# pads.net
KiCad netlist of a schematic drawn in EAGLE
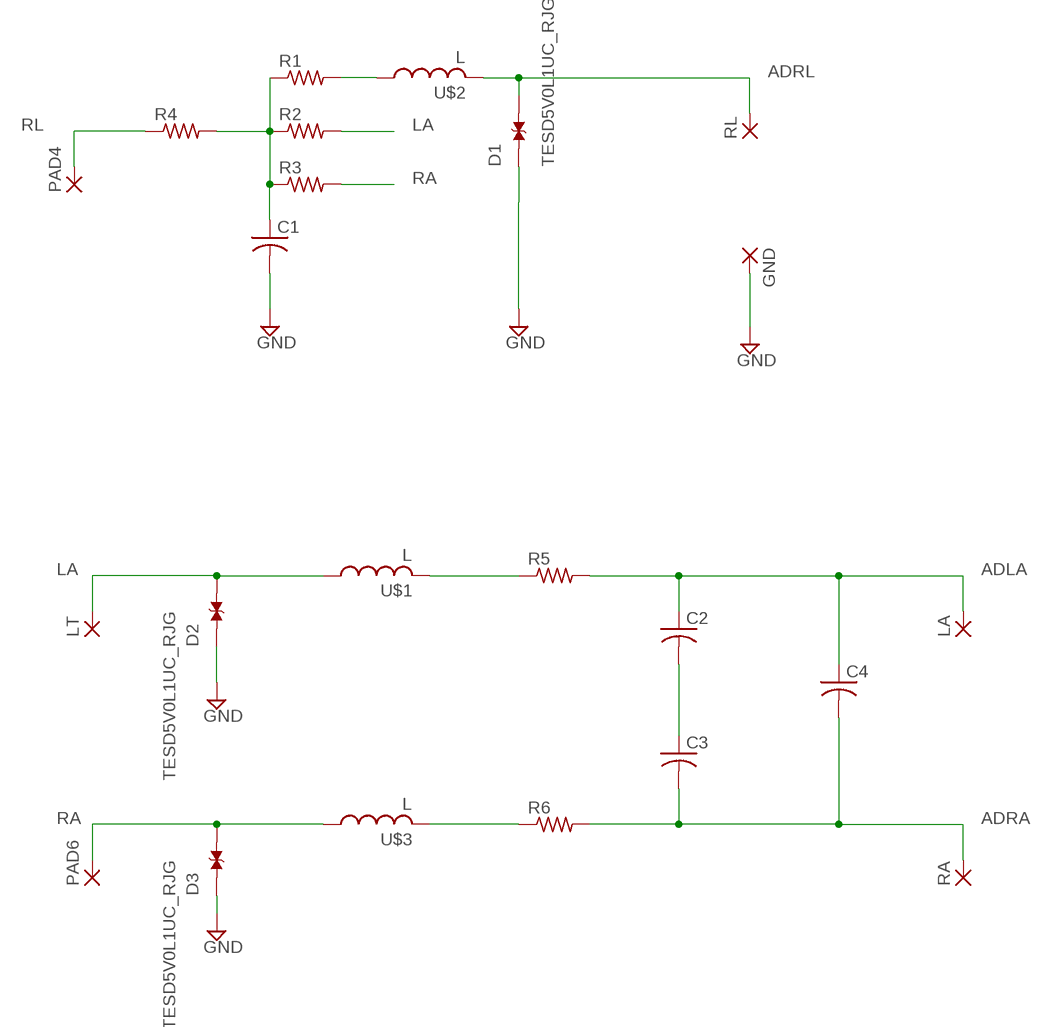
[diagram p0: schematic, sheet 1]

(export (version "E")
  (design (tool "Eeschema 10.0.6"))
  (components
    (comp (ref "C1")
      (value "C-US025-024X044")
      (footprint "eagle-import:C025-024X044")
      (libsource (lib "eagle-import") (part "C-US025-024X044"))
    )
    (comp (ref "C2")
      (value "C-US025-024X044")
      (footprint "eagle-import:C025-024X044")
      (libsource (lib "eagle-import") (part "C-US025-024X044"))
    )
    (comp (ref "C3")
      (value "C-US025-024X044")
      (footprint "eagle-import:C025-024X044")
      (libsource (lib "eagle-import") (part "C-US025-024X044"))
    )
    (comp (ref "C4")
      (value "C-US025-024X044")
      (footprint "eagle-import:C025-024X044")
      (libsource (lib "eagle-import") (part "C-US025-024X044"))
    )
    (comp (ref "D1")
      (value "TESD5V0L1UC_RJG")
      (footprint "eagle-import:DIO_TESD5V0L1UC_RJG")
      (fields (field (name "MF") "Taiwan Semiconductor Corporation") (field (name "MP") "TESD5V0L1UC RJG"))
      (libsource (lib "eagle-import") (part "TESD5V0L1UC_RJG"))
    )
    (comp (ref "D2")
      (value "TESD5V0L1UC_RJG")
      (footprint "eagle-import:DIO_TESD5V0L1UC_RJG")
      (fields (field (name "MF") "Taiwan Semiconductor Corporation") (field (name "MP") "TESD5V0L1UC RJG"))
      (libsource (lib "eagle-import") (part "TESD5V0L1UC_RJG"))
    )
    (comp (ref "D3")
      (value "TESD5V0L1UC_RJG")
      (footprint "eagle-import:DIO_TESD5V0L1UC_RJG")
      (fields (field (name "MF") "Taiwan Semiconductor Corporation") (field (name "MP") "TESD5V0L1UC RJG"))
      (libsource (lib "eagle-import") (part "TESD5V0L1UC_RJG"))
    )
    (comp (ref "GND")
      (value "2,15/1,0")
      (footprint "eagle-import:2,15_1,0")
      (libsource (lib "eagle-import") (part "2,15/1,0"))
    )
    (comp (ref "LA")
      (value "2,15/1,0")
      (footprint "eagle-import:2,15_1,0")
      (libsource (lib "eagle-import") (part "2,15/1,0"))
    )
    (comp (ref "LT")
      (value "SMD5")
      (footprint "eagle-import:SMD2,54-5,08")
      (libsource (lib "eagle-import") (part "SMD5"))
    )
    (comp (ref "PAD4")
      (value "SMD5")
      (footprint "eagle-import:SMD2,54-5,08")
      (libsource (lib "eagle-import") (part "SMD5"))
    )
    (comp (ref "PAD6")
      (value "SMD5")
      (footprint "eagle-import:SMD2,54-5,08")
      (libsource (lib "eagle-import") (part "SMD5"))
    )
    (comp (ref "R1")
      (value "R-US_0207/10")
      (footprint "eagle-import:0207_10")
      (libsource (lib "eagle-import") (part "R-US_0207/10"))
    )
    (comp (ref "R2")
      (value "R-US_0207/10")
      (footprint "eagle-import:0207_10")
      (libsource (lib "eagle-import") (part "R-US_0207/10"))
    )
    (comp (ref "R3")
      (value "R-US_0207/10")
      (footprint "eagle-import:0207_10")
      (libsource (lib "eagle-import") (part "R-US_0207/10"))
    )
    (comp (ref "R4")
      (value "R-US_0207/10")
      (footprint "eagle-import:0207_10")
      (libsource (lib "eagle-import") (part "R-US_0207/10"))
    )
    (comp (ref "R5")
      (value "R-US_0207/10")
      (footprint "eagle-import:0207_10")
      (libsource (lib "eagle-import") (part "R-US_0207/10"))
    )
    (comp (ref "R6")
      (value "R-US_0207/10")
      (footprint "eagle-import:0207_10")
      (libsource (lib "eagle-import") (part "R-US_0207/10"))
    )
    (comp (ref "RA")
      (value "2,15/1,0")
      (footprint "eagle-import:2,15_1,0")
      (libsource (lib "eagle-import") (part "2,15/1,0"))
    )
    (comp (ref "RL")
      (value "2,15/1,0")
      (footprint "eagle-import:2,15_1,0")
      (libsource (lib "eagle-import") (part "2,15/1,0"))
    )
    (comp (ref "U$1") (value "L") (footprint "eagle-import:6000") (libsource (lib "eagle-import") (part "L")))
    (comp (ref "U$2") (value "L") (footprint "eagle-import:6000") (libsource (lib "eagle-import") (part "L")))
    (comp (ref "U$3") (value "L") (footprint "eagle-import:6000") (libsource (lib "eagle-import") (part "L")))
  )
  (nets
    (net (code "1") (name "/ADLA") (class "Default")
      (node (ref "C2") (pin "1") (pinfunction "1_1") (pintype "passive"))
      (node (ref "C4") (pin "1") (pinfunction "1_1") (pintype "passive"))
      (node (ref "LA") (pin "1") (pinfunction "P_1") (pintype "passive"))
      (node (ref "R5") (pin "2") (pinfunction "2_2") (pintype "passive"))
    )
    (net (code "2") (name "/ADRA") (class "Default")
      (node (ref "C3") (pin "2") (pinfunction "2_2") (pintype "passive"))
      (node (ref "C4") (pin "2") (pinfunction "2_2") (pintype "passive"))
      (node (ref "R6") (pin "2") (pinfunction "2_2") (pintype "passive"))
      (node (ref "RA") (pin "1") (pinfunction "P_1") (pintype "passive"))
    )
    (net (code "3") (name "/ADRL") (class "Default")
      (node (ref "D1") (pin "2") (pinfunction "2_2") (pintype "passive"))
      (node (ref "RL") (pin "1") (pinfunction "P_1") (pintype "passive"))
      (node (ref "U$2") (pin "2") (pinfunction "2_2") (pintype "passive"))
    )
    (net (code "4") (name "/LA") (class "Default")
      (node (ref "D2") (pin "2") (pinfunction "2_2") (pintype "passive"))
      (node (ref "LT") (pin "1") (pinfunction "P_1") (pintype "passive"))
      (node (ref "R2") (pin "2") (pinfunction "2_2") (pintype "passive"))
      (node (ref "U$1") (pin "1") (pinfunction "1_1") (pintype "passive"))
    )
    (net (code "5") (name "/RA") (class "Default")
      (node (ref "D3") (pin "2") (pinfunction "2_2") (pintype "passive"))
      (node (ref "PAD6") (pin "1") (pinfunction "P_1") (pintype "passive"))
      (node (ref "R3") (pin "2") (pinfunction "2_2") (pintype "passive"))
      (node (ref "U$3") (pin "1") (pinfunction "1_1") (pintype "passive"))
    )
    (net (code "6") (name "/RL") (class "Default")
      (node (ref "PAD4") (pin "1") (pinfunction "P_1") (pintype "passive"))
      (node (ref "R4") (pin "1") (pinfunction "1_1") (pintype "passive"))
    )
    (net (code "7") (name "GND") (class "Default")
      (node (ref "C1") (pin "2") (pinfunction "2_2") (pintype "passive"))
      (node (ref "D1") (pin "1") (pinfunction "1_1") (pintype "passive"))
      (node (ref "D2") (pin "1") (pinfunction "1_1") (pintype "passive"))
      (node (ref "D3") (pin "1") (pinfunction "1_1") (pintype "passive"))
      (node (ref "GND") (pin "1") (pinfunction "P_1") (pintype "passive"))
    )
    (net (code "8") (name "Net-(C1-Pad1)") (class "Default")
      (node (ref "C1") (pin "1") (pinfunction "1_1") (pintype "passive"))
      (node (ref "R1") (pin "1") (pinfunction "1_1") (pintype "passive"))
      (node (ref "R2") (pin "1") (pinfunction "1_1") (pintype "passive"))
      (node (ref "R3") (pin "1") (pinfunction "1_1") (pintype "passive"))
      (node (ref "R4") (pin "2") (pinfunction "2_2") (pintype "passive"))
    )
    (net (code "9") (name "Net-(C2-Pad2)") (class "Default")
      (node (ref "C2") (pin "2") (pinfunction "2_2") (pintype "passive"))
      (node (ref "C3") (pin "1") (pinfunction "1_1") (pintype "passive"))
    )
    (net (code "10") (name "Net-(R1-Pad2)") (class "Default")
      (node (ref "R1") (pin "2") (pinfunction "2_2") (pintype "passive"))
      (node (ref "U$2") (pin "1") (pinfunction "1_1") (pintype "passive"))
    )
    (net (code "11") (name "Net-(R5-Pad1)") (class "Default")
      (node (ref "R5") (pin "1") (pinfunction "1_1") (pintype "passive"))
      (node (ref "U$1") (pin "2") (pinfunction "2_2") (pintype "passive"))
    )
    (net (code "12") (name "Net-(R6-Pad1)") (class "Default")
      (node (ref "R6") (pin "1") (pinfunction "1_1") (pintype "passive"))
      (node (ref "U$3") (pin "2") (pinfunction "2_2") (pintype "passive"))
    )
  )
)
